# E17-15-CHARGE_SW.net
KiCad netlist of a schematic drawn in Altium Designer
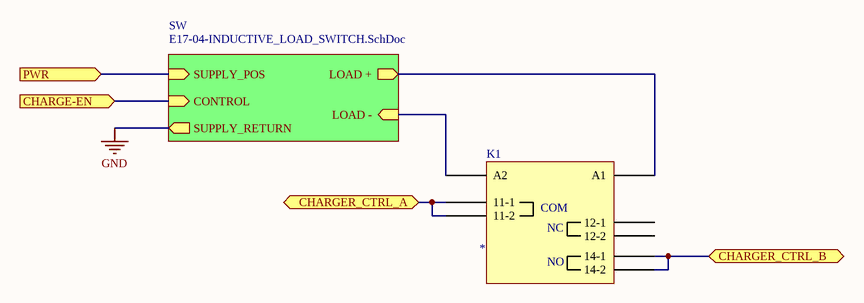
[diagram p0: E17-15-CHARGE_SW.SchDoc]

(export (version "E")
  (design (tool "Eeschema 10.0.6"))
  (components
    (comp (ref "K1")
      (value "*")
      (footprint "TE-7-1393243-5")
      (description "RELAY GEN PURPOSE SPDT 16A 110V")
      (libsource (lib "E17-12_CC") (part "TE-1393240-3"))
    )
  )
  (nets
    (net (code "2") (name "/CHARGER_CTRL_A") (class "Default")
      (node (ref "K1") (pin "3") (pinfunction "11-1_3") (pintype "passive"))
      (node (ref "K1") (pin "6") (pinfunction "11-2_6") (pintype "passive"))
    )
    (net (code "3") (name "/CHARGER_CTRL_B") (class "Default")
      (node (ref "K1") (pin "4") (pinfunction "14-1_4") (pintype "passive"))
      (node (ref "K1") (pin "5") (pinfunction "14-2_5") (pintype "passive"))
    )
    (net (code "4") (name "/LOAD +") (class "Default")
      (node (ref "K1") (pin "8") (pinfunction "A1_8") (pintype "passive"))
    )
    (net (code "5") (name "/LOAD -") (class "Default")
      (node (ref "K1") (pin "1") (pinfunction "A2_1") (pintype "passive"))
    )
    (net (code "8") (name "unconnected-(K1-12-1-Pad2)") (class "Default")
      (node (ref "K1") (pin "2") (pinfunction "12-1_2") (pintype "passive"))
    )
    (net (code "9") (name "unconnected-(K1-12-2-Pad7)") (class "Default")
      (node (ref "K1") (pin "7") (pinfunction "12-2_7") (pintype "passive"))
    )
  )
)
